# Test_shema.net
KiCad netlist of a schematic drawn in Altium Designer
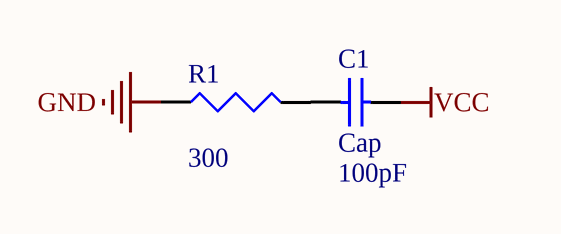
[diagram p0: Test_shema.SchDoc]

(export (version "E")
  (design (tool "Eeschema 10.0.6"))
  (components
    (comp (ref "C1")
      (value "Cap")
      (footprint "Capacitor 1206")
      (description "Capacitor")
      (fields (field (name "ALTIUM_VALUE") "100pF") (field (name "PUBLISHER") "Altium Limited"))
      (libsource (lib "Miscellaneous Devices") (part "Cap"))
    )
    (comp (ref "R1")
      (value "300")
      (footprint "Resistor 1206")
      (description "Resistor")
      (fields (field (name "PUBLISHER") "Altium Limited"))
      (libsource (lib "Miscellaneous Devices") (part "Res3"))
    )
  )
  (nets
    (net (code "1") (name "GND") (class "Default")
      (node (ref "R1") (pin "1") (pinfunction "1_1") (pintype "passive"))
    )
    (net (code "2") (name "Net-(C1-Pad1)") (class "Default")
      (node (ref "C1") (pin "1") (pinfunction "1_1") (pintype "passive"))
      (node (ref "R1") (pin "2") (pinfunction "2_2") (pintype "passive"))
    )
    (net (code "3") (name "VCC") (class "Default")
      (node (ref "C1") (pin "2") (pinfunction "2_2") (pintype "passive"))
    )
  )
)
